# main.net
KiCad netlist of a schematic drawn in EAGLE
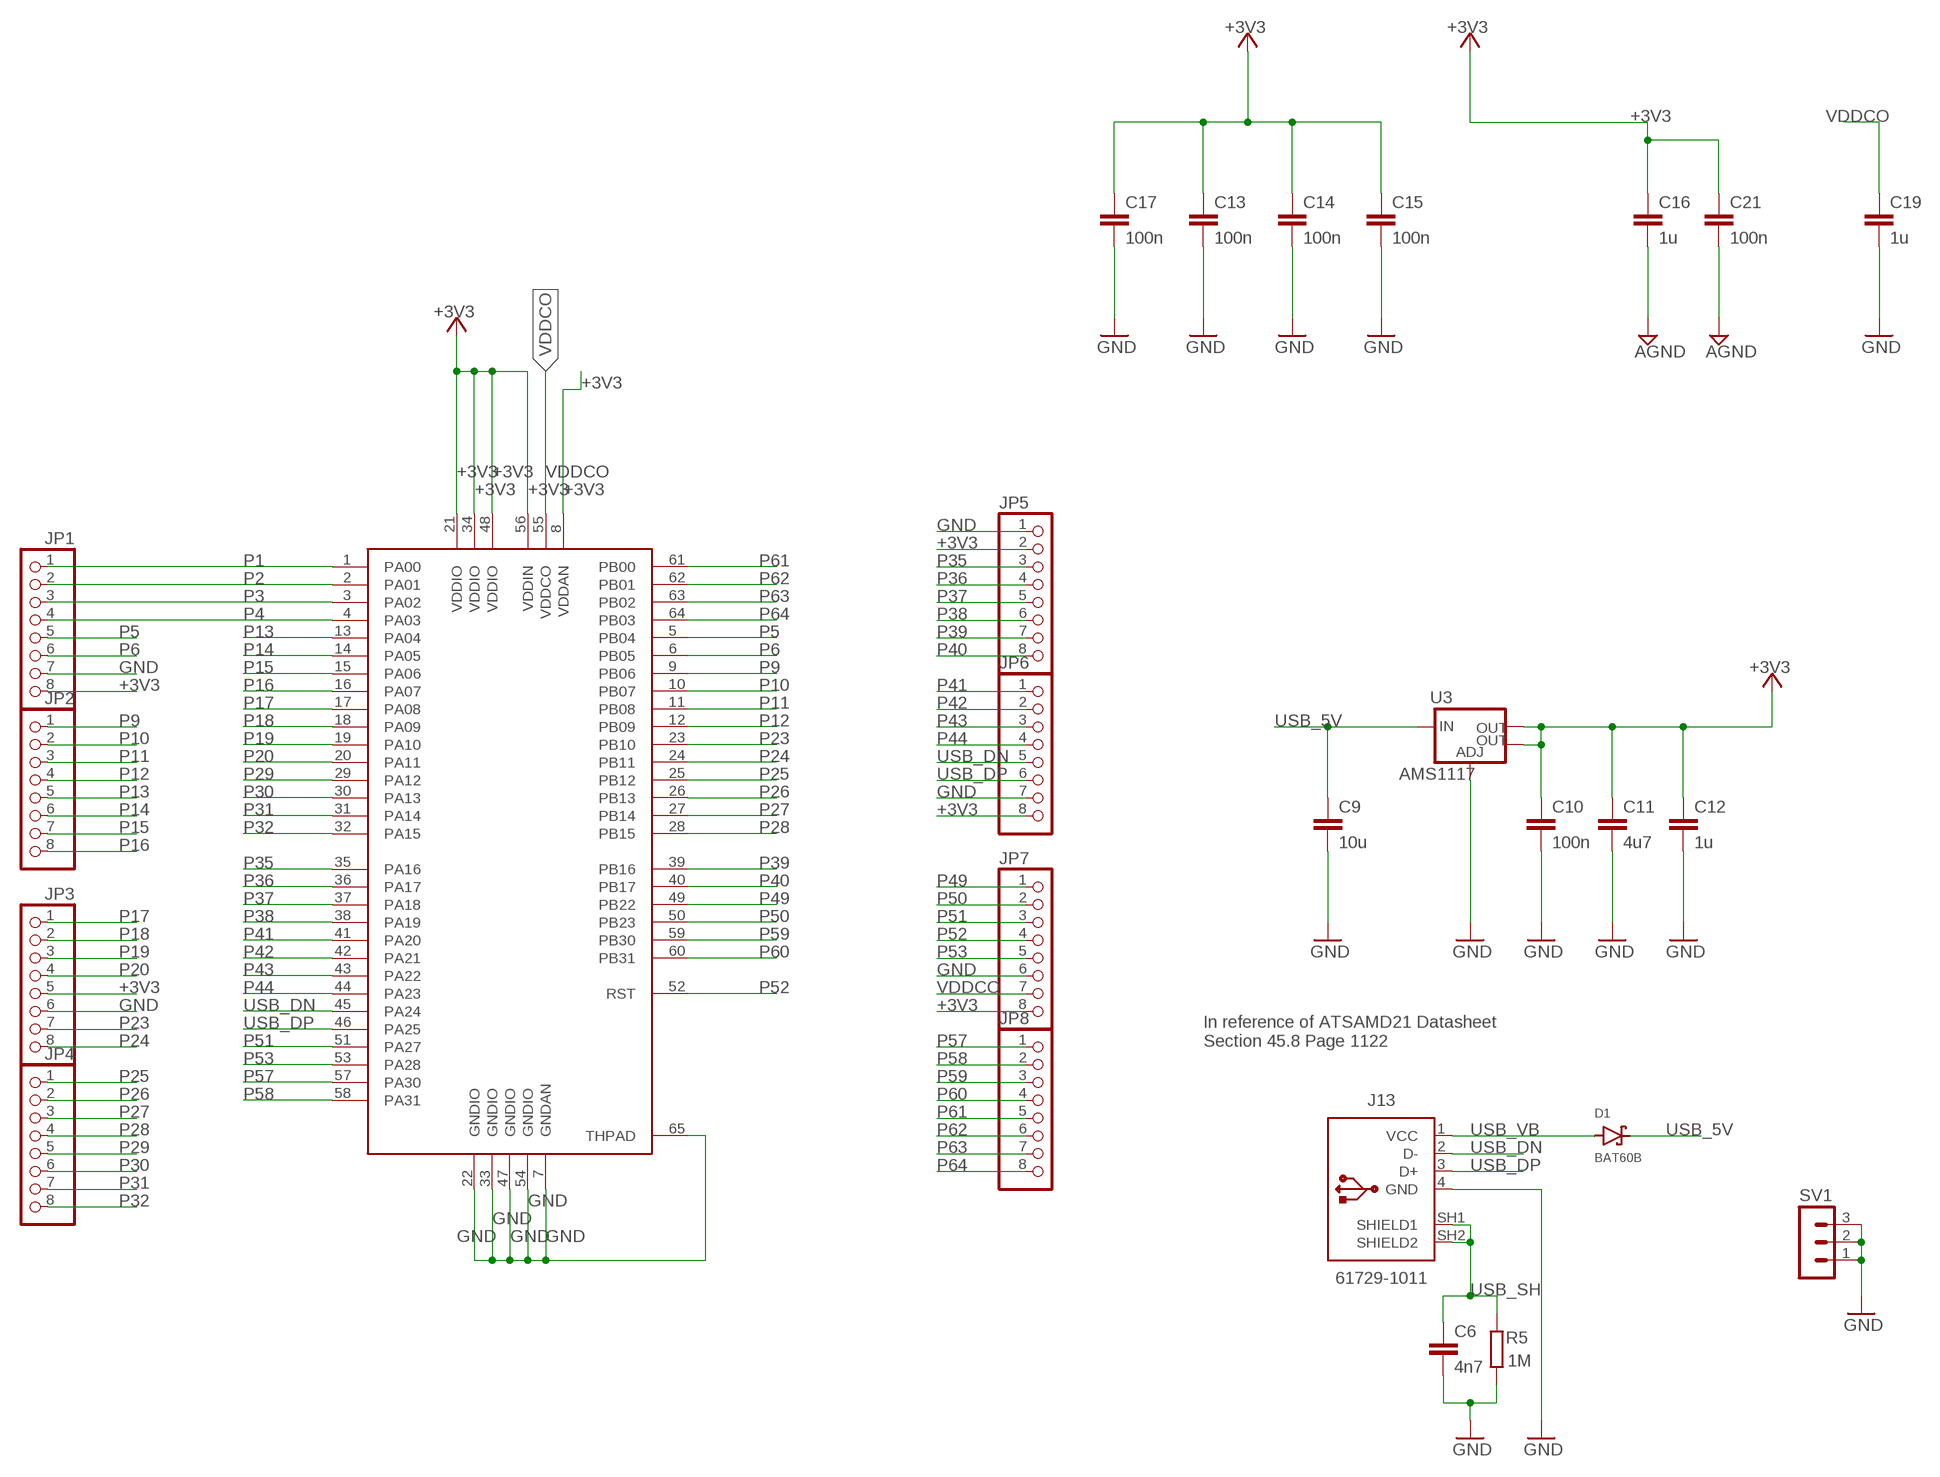
[diagram p0: schematic, sheet 1]

(export (version "E")
  (design (tool "Eeschema 10.0.6"))
  (components
    (comp (ref "C6")
      (value "4n7")
      (footprint "eagle-import:C0603")
      (libsource (lib "eagle-import") (part "C-EUC0603"))
    )
    (comp (ref "C9")
      (value "10u")
      (footprint "eagle-import:C0603")
      (libsource (lib "eagle-import") (part "C-EUC0603"))
    )
    (comp (ref "C10")
      (value "100n")
      (footprint "eagle-import:C0603")
      (libsource (lib "eagle-import") (part "C-EUC0603"))
    )
    (comp (ref "C11")
      (value "4u7")
      (footprint "eagle-import:C0603")
      (libsource (lib "eagle-import") (part "C-EUC0603"))
    )
    (comp (ref "C12")
      (value "1u")
      (footprint "eagle-import:C0603")
      (libsource (lib "eagle-import") (part "C-EUC0603"))
    )
    (comp (ref "C13")
      (value "100n")
      (footprint "eagle-import:C0603")
      (libsource (lib "eagle-import") (part "C-EUC0603"))
    )
    (comp (ref "C14")
      (value "100n")
      (footprint "eagle-import:C0603")
      (libsource (lib "eagle-import") (part "C-EUC0603"))
    )
    (comp (ref "C15")
      (value "100n")
      (footprint "eagle-import:C0603")
      (libsource (lib "eagle-import") (part "C-EUC0603"))
    )
    (comp (ref "C16")
      (value "1u")
      (footprint "eagle-import:C0603")
      (libsource (lib "eagle-import") (part "C-EUC0603"))
    )
    (comp (ref "C17")
      (value "100n")
      (footprint "eagle-import:C0603")
      (libsource (lib "eagle-import") (part "C-EUC0603"))
    )
    (comp (ref "C19")
      (value "1u")
      (footprint "eagle-import:C0603")
      (libsource (lib "eagle-import") (part "C-EUC0603"))
    )
    (comp (ref "C21")
      (value "100n")
      (footprint "eagle-import:C0603")
      (libsource (lib "eagle-import") (part "C-EUC0603"))
    )
    (comp (ref "D1")
      (value "BAT60B")
      (footprint "eagle-import:DO41-7.6")
      (libsource (lib "eagle-import") (part "1N5817-B"))
    )
    (comp (ref "J13")
      (value "61729-1011")
      (footprint "eagle-import:61729-1011BLF")
      (fields (field (name "MANUFACTURER") "Amphenol ICC (FCI)") (field (name "MPN") "61729-1011BLF"))
      (libsource (lib "eagle-import") (part "61729-1011"))
    )
    (comp (ref "JP1")
      (value "PINHD-1X8CLEANBIG")
      (footprint "eagle-import:1X08-CLEANBIG")
      (libsource (lib "eagle-import") (part "PINHD-1X8CLEANBIG"))
    )
    (comp (ref "JP2")
      (value "PINHD-1X8CLEANBIG")
      (footprint "eagle-import:1X08-CLEANBIG")
      (libsource (lib "eagle-import") (part "PINHD-1X8CLEANBIG"))
    )
    (comp (ref "JP3")
      (value "PINHD-1X8CLEANBIG")
      (footprint "eagle-import:1X08-CLEANBIG")
      (libsource (lib "eagle-import") (part "PINHD-1X8CLEANBIG"))
    )
    (comp (ref "JP4")
      (value "PINHD-1X8CLEANBIG")
      (footprint "eagle-import:1X08-CLEANBIG")
      (libsource (lib "eagle-import") (part "PINHD-1X8CLEANBIG"))
    )
    (comp (ref "JP5")
      (value "PINHD-1X8CLEANBIG")
      (footprint "eagle-import:1X08-CLEANBIG")
      (libsource (lib "eagle-import") (part "PINHD-1X8CLEANBIG"))
    )
    (comp (ref "JP6")
      (value "PINHD-1X8CLEANBIG")
      (footprint "eagle-import:1X08-CLEANBIG")
      (libsource (lib "eagle-import") (part "PINHD-1X8CLEANBIG"))
    )
    (comp (ref "JP7")
      (value "PINHD-1X8CLEANBIG")
      (footprint "eagle-import:1X08-CLEANBIG")
      (libsource (lib "eagle-import") (part "PINHD-1X8CLEANBIG"))
    )
    (comp (ref "JP8")
      (value "PINHD-1X8CLEANBIG")
      (footprint "eagle-import:1X08-CLEANBIG")
      (libsource (lib "eagle-import") (part "PINHD-1X8CLEANBIG"))
    )
    (comp (ref "R5")
      (value "1M")
      (footprint "eagle-import:R0603")
      (libsource (lib "eagle-import") (part "R-EU_R0603"))
    )
    (comp (ref "SV1")
      (value "MA03-1")
      (footprint "eagle-import:MA03-1")
      (libsource (lib "eagle-import") (part "MA03-1"))
    )
    (comp (ref "U$1")
      (value "ATSAMD21J18AQFN64")
      (footprint "eagle-import:QFN50P900X900X100-65T535")
      (libsource (lib "eagle-import") (part "ATSAMD21J18AQFN64"))
    )
    (comp (ref "U3")
      (value "AMS1117")
      (footprint "eagle-import:SOT223")
      (libsource (lib "eagle-import") (part "V_REG_LM1117SOT223"))
    )
  )
  (nets
    (net (code "1") (name "+3V3") (class "Default")
      (node (ref "C10") (pin "1") (pinfunction "1_1") (pintype "passive"))
      (node (ref "C11") (pin "1") (pinfunction "1_1") (pintype "passive"))
      (node (ref "C12") (pin "1") (pinfunction "1_1") (pintype "passive"))
      (node (ref "C13") (pin "1") (pinfunction "1_1") (pintype "passive"))
      (node (ref "C14") (pin "1") (pinfunction "1_1") (pintype "passive"))
      (node (ref "C15") (pin "1") (pinfunction "1_1") (pintype "passive"))
      (node (ref "C16") (pin "1") (pinfunction "1_1") (pintype "passive"))
      (node (ref "C17") (pin "1") (pinfunction "1_1") (pintype "passive"))
      (node (ref "C21") (pin "1") (pinfunction "1_1") (pintype "passive"))
      (node (ref "JP1") (pin "8") (pinfunction "8_8") (pintype "passive"))
      (node (ref "JP3") (pin "5") (pinfunction "5_5") (pintype "passive"))
      (node (ref "JP5") (pin "2") (pinfunction "2_2") (pintype "passive"))
      (node (ref "JP6") (pin "8") (pinfunction "8_8") (pintype "passive"))
      (node (ref "JP7") (pin "8") (pinfunction "8_8") (pintype "passive"))
      (node (ref "U$1") (pin "21") (pinfunction "VDDIO_21") (pintype "bidirectional"))
      (node (ref "U$1") (pin "34") (pinfunction "VDDIO_34") (pintype "bidirectional"))
      (node (ref "U$1") (pin "48") (pinfunction "VDDIO_48") (pintype "bidirectional"))
      (node (ref "U$1") (pin "56") (pinfunction "VDDIN_56") (pintype "bidirectional"))
      (node (ref "U$1") (pin "8") (pinfunction "VDDAN_8") (pintype "bidirectional"))
      (node (ref "U3") (pin "2") (pinfunction "OUT_2") (pintype "output"))
      (node (ref "U3") (pin "4") (pinfunction "OUT_4") (pintype "output"))
    )
    (net (code "2") (name "/P1") (class "Default")
      (node (ref "JP1") (pin "1") (pinfunction "1_1") (pintype "passive"))
      (node (ref "U$1") (pin "1") (pinfunction "PA00_1") (pintype "bidirectional"))
    )
    (net (code "3") (name "/P2") (class "Default")
      (node (ref "JP1") (pin "2") (pinfunction "2_2") (pintype "passive"))
      (node (ref "U$1") (pin "2") (pinfunction "PA01_2") (pintype "bidirectional"))
    )
    (net (code "4") (name "/P3") (class "Default")
      (node (ref "JP1") (pin "3") (pinfunction "3_3") (pintype "passive"))
      (node (ref "U$1") (pin "3") (pinfunction "PA02_3") (pintype "bidirectional"))
    )
    (net (code "5") (name "/P4") (class "Default")
      (node (ref "JP1") (pin "4") (pinfunction "4_4") (pintype "passive"))
      (node (ref "U$1") (pin "4") (pinfunction "PA03_4") (pintype "bidirectional"))
    )
    (net (code "6") (name "/P5") (class "Default")
      (node (ref "JP1") (pin "5") (pinfunction "5_5") (pintype "passive"))
      (node (ref "U$1") (pin "5") (pinfunction "PB04_5") (pintype "bidirectional"))
    )
    (net (code "7") (name "/P6") (class "Default")
      (node (ref "JP1") (pin "6") (pinfunction "6_6") (pintype "passive"))
      (node (ref "U$1") (pin "6") (pinfunction "PB05_6") (pintype "bidirectional"))
    )
    (net (code "8") (name "/P9") (class "Default")
      (node (ref "JP2") (pin "1") (pinfunction "1_1") (pintype "passive"))
      (node (ref "U$1") (pin "9") (pinfunction "PB06_9") (pintype "bidirectional"))
    )
    (net (code "9") (name "/P10") (class "Default")
      (node (ref "JP2") (pin "2") (pinfunction "2_2") (pintype "passive"))
      (node (ref "U$1") (pin "10") (pinfunction "PB07_10") (pintype "bidirectional"))
    )
    (net (code "10") (name "/P11") (class "Default")
      (node (ref "JP2") (pin "3") (pinfunction "3_3") (pintype "passive"))
      (node (ref "U$1") (pin "11") (pinfunction "PB08_11") (pintype "bidirectional"))
    )
    (net (code "11") (name "/P12") (class "Default")
      (node (ref "JP2") (pin "4") (pinfunction "4_4") (pintype "passive"))
      (node (ref "U$1") (pin "12") (pinfunction "PB09_12") (pintype "bidirectional"))
    )
    (net (code "12") (name "/P13") (class "Default")
      (node (ref "JP2") (pin "5") (pinfunction "5_5") (pintype "passive"))
      (node (ref "U$1") (pin "13") (pinfunction "PA04_13") (pintype "bidirectional"))
    )
    (net (code "13") (name "/P14") (class "Default")
      (node (ref "JP2") (pin "6") (pinfunction "6_6") (pintype "passive"))
      (node (ref "U$1") (pin "14") (pinfunction "PA05_14") (pintype "bidirectional"))
    )
    (net (code "14") (name "/P15") (class "Default")
      (node (ref "JP2") (pin "7") (pinfunction "7_7") (pintype "passive"))
      (node (ref "U$1") (pin "15") (pinfunction "PA06_15") (pintype "bidirectional"))
    )
    (net (code "15") (name "/P16") (class "Default")
      (node (ref "JP2") (pin "8") (pinfunction "8_8") (pintype "passive"))
      (node (ref "U$1") (pin "16") (pinfunction "PA07_16") (pintype "bidirectional"))
    )
    (net (code "16") (name "/P17") (class "Default")
      (node (ref "JP3") (pin "1") (pinfunction "1_1") (pintype "passive"))
      (node (ref "U$1") (pin "17") (pinfunction "PA08_17") (pintype "bidirectional"))
    )
    (net (code "17") (name "/P18") (class "Default")
      (node (ref "JP3") (pin "2") (pinfunction "2_2") (pintype "passive"))
      (node (ref "U$1") (pin "18") (pinfunction "PA09_18") (pintype "bidirectional"))
    )
    (net (code "18") (name "/P19") (class "Default")
      (node (ref "JP3") (pin "3") (pinfunction "3_3") (pintype "passive"))
      (node (ref "U$1") (pin "19") (pinfunction "PA10_19") (pintype "bidirectional"))
    )
    (net (code "19") (name "/P20") (class "Default")
      (node (ref "JP3") (pin "4") (pinfunction "4_4") (pintype "passive"))
      (node (ref "U$1") (pin "20") (pinfunction "PA11_20") (pintype "bidirectional"))
    )
    (net (code "20") (name "/P23") (class "Default")
      (node (ref "JP3") (pin "7") (pinfunction "7_7") (pintype "passive"))
      (node (ref "U$1") (pin "23") (pinfunction "PB10_23") (pintype "bidirectional"))
    )
    (net (code "21") (name "/P24") (class "Default")
      (node (ref "JP3") (pin "8") (pinfunction "8_8") (pintype "passive"))
      (node (ref "U$1") (pin "24") (pinfunction "PB11_24") (pintype "bidirectional"))
    )
    (net (code "22") (name "/P25") (class "Default")
      (node (ref "JP4") (pin "1") (pinfunction "1_1") (pintype "passive"))
      (node (ref "U$1") (pin "25") (pinfunction "PB12_25") (pintype "bidirectional"))
    )
    (net (code "23") (name "/P26") (class "Default")
      (node (ref "JP4") (pin "2") (pinfunction "2_2") (pintype "passive"))
      (node (ref "U$1") (pin "26") (pinfunction "PB13_26") (pintype "bidirectional"))
    )
    (net (code "24") (name "/P27") (class "Default")
      (node (ref "JP4") (pin "3") (pinfunction "3_3") (pintype "passive"))
      (node (ref "U$1") (pin "27") (pinfunction "PB14_27") (pintype "bidirectional"))
    )
    (net (code "25") (name "/P28") (class "Default")
      (node (ref "JP4") (pin "4") (pinfunction "4_4") (pintype "passive"))
      (node (ref "U$1") (pin "28") (pinfunction "PB15_28") (pintype "bidirectional"))
    )
    (net (code "26") (name "/P29") (class "Default")
      (node (ref "JP4") (pin "5") (pinfunction "5_5") (pintype "passive"))
      (node (ref "U$1") (pin "29") (pinfunction "PA12_29") (pintype "bidirectional"))
    )
    (net (code "27") (name "/P30") (class "Default")
      (node (ref "JP4") (pin "6") (pinfunction "6_6") (pintype "passive"))
      (node (ref "U$1") (pin "30") (pinfunction "PA13_30") (pintype "bidirectional"))
    )
    (net (code "28") (name "/P31") (class "Default")
      (node (ref "JP4") (pin "7") (pinfunction "7_7") (pintype "passive"))
      (node (ref "U$1") (pin "31") (pinfunction "PA14_31") (pintype "bidirectional"))
    )
    (net (code "29") (name "/P32") (class "Default")
      (node (ref "JP4") (pin "8") (pinfunction "8_8") (pintype "passive"))
      (node (ref "U$1") (pin "32") (pinfunction "PA15_32") (pintype "bidirectional"))
    )
    (net (code "30") (name "/P35") (class "Default")
      (node (ref "JP5") (pin "3") (pinfunction "3_3") (pintype "passive"))
      (node (ref "U$1") (pin "35") (pinfunction "PA16_35") (pintype "bidirectional"))
    )
    (net (code "31") (name "/P36") (class "Default")
      (node (ref "JP5") (pin "4") (pinfunction "4_4") (pintype "passive"))
      (node (ref "U$1") (pin "36") (pinfunction "PA17_36") (pintype "bidirectional"))
    )
    (net (code "32") (name "/P37") (class "Default")
      (node (ref "JP5") (pin "5") (pinfunction "5_5") (pintype "passive"))
      (node (ref "U$1") (pin "37") (pinfunction "PA18_37") (pintype "bidirectional"))
    )
    (net (code "33") (name "/P38") (class "Default")
      (node (ref "JP5") (pin "6") (pinfunction "6_6") (pintype "passive"))
      (node (ref "U$1") (pin "38") (pinfunction "PA19_38") (pintype "bidirectional"))
    )
    (net (code "34") (name "/P39") (class "Default")
      (node (ref "JP5") (pin "7") (pinfunction "7_7") (pintype "passive"))
      (node (ref "U$1") (pin "39") (pinfunction "PB16_39") (pintype "bidirectional"))
    )
    (net (code "35") (name "/P40") (class "Default")
      (node (ref "JP5") (pin "8") (pinfunction "8_8") (pintype "passive"))
      (node (ref "U$1") (pin "40") (pinfunction "PB17_40") (pintype "bidirectional"))
    )
    (net (code "36") (name "/P41") (class "Default")
      (node (ref "JP6") (pin "1") (pinfunction "1_1") (pintype "passive"))
      (node (ref "U$1") (pin "41") (pinfunction "PA20_41") (pintype "bidirectional"))
    )
    (net (code "37") (name "/P42") (class "Default")
      (node (ref "JP6") (pin "2") (pinfunction "2_2") (pintype "passive"))
      (node (ref "U$1") (pin "42") (pinfunction "PA21_42") (pintype "bidirectional"))
    )
    (net (code "38") (name "/P43") (class "Default")
      (node (ref "JP6") (pin "3") (pinfunction "3_3") (pintype "passive"))
      (node (ref "U$1") (pin "43") (pinfunction "PA22_43") (pintype "bidirectional"))
    )
    (net (code "39") (name "/P44") (class "Default")
      (node (ref "JP6") (pin "4") (pinfunction "4_4") (pintype "passive"))
      (node (ref "U$1") (pin "44") (pinfunction "PA23_44") (pintype "bidirectional"))
    )
    (net (code "40") (name "/P49") (class "Default")
      (node (ref "JP7") (pin "1") (pinfunction "1_1") (pintype "passive"))
      (node (ref "U$1") (pin "49") (pinfunction "PB22_49") (pintype "bidirectional"))
    )
    (net (code "41") (name "/P50") (class "Default")
      (node (ref "JP7") (pin "2") (pinfunction "2_2") (pintype "passive"))
      (node (ref "U$1") (pin "50") (pinfunction "PB23_50") (pintype "bidirectional"))
    )
    (net (code "42") (name "/P51") (class "Default")
      (node (ref "JP7") (pin "3") (pinfunction "3_3") (pintype "passive"))
      (node (ref "U$1") (pin "51") (pinfunction "PA27_51") (pintype "bidirectional"))
    )
    (net (code "43") (name "/P52") (class "Default")
      (node (ref "JP7") (pin "4") (pinfunction "4_4") (pintype "passive"))
      (node (ref "U$1") (pin "52") (pinfunction "RST_52") (pintype "bidirectional"))
    )
    (net (code "44") (name "/P53") (class "Default")
      (node (ref "JP7") (pin "5") (pinfunction "5_5") (pintype "passive"))
      (node (ref "U$1") (pin "53") (pinfunction "PA28_53") (pintype "bidirectional"))
    )
    (net (code "45") (name "/P57") (class "Default")
      (node (ref "JP8") (pin "1") (pinfunction "1_1") (pintype "passive"))
      (node (ref "U$1") (pin "57") (pinfunction "PA30_57") (pintype "bidirectional"))
    )
    (net (code "46") (name "/P58") (class "Default")
      (node (ref "JP8") (pin "2") (pinfunction "2_2") (pintype "passive"))
      (node (ref "U$1") (pin "58") (pinfunction "PA31_58") (pintype "bidirectional"))
    )
    (net (code "47") (name "/P59") (class "Default")
      (node (ref "JP8") (pin "3") (pinfunction "3_3") (pintype "passive"))
      (node (ref "U$1") (pin "59") (pinfunction "PB30_59") (pintype "bidirectional"))
    )
    (net (code "48") (name "/P60") (class "Default")
      (node (ref "JP8") (pin "4") (pinfunction "4_4") (pintype "passive"))
      (node (ref "U$1") (pin "60") (pinfunction "PB31_60") (pintype "bidirectional"))
    )
    (net (code "49") (name "/P61") (class "Default")
      (node (ref "JP8") (pin "5") (pinfunction "5_5") (pintype "passive"))
      (node (ref "U$1") (pin "61") (pinfunction "PB00_61") (pintype "bidirectional"))
    )
    (net (code "50") (name "/P62") (class "Default")
      (node (ref "JP8") (pin "6") (pinfunction "6_6") (pintype "passive"))
      (node (ref "U$1") (pin "62") (pinfunction "PB01_62") (pintype "bidirectional"))
    )
    (net (code "51") (name "/P63") (class "Default")
      (node (ref "JP8") (pin "7") (pinfunction "7_7") (pintype "passive"))
      (node (ref "U$1") (pin "63") (pinfunction "PB02_63") (pintype "bidirectional"))
    )
    (net (code "52") (name "/P64") (class "Default")
      (node (ref "JP8") (pin "8") (pinfunction "8_8") (pintype "passive"))
      (node (ref "U$1") (pin "64") (pinfunction "PB03_64") (pintype "bidirectional"))
    )
    (net (code "53") (name "/USB_5V") (class "Default")
      (node (ref "C9") (pin "1") (pinfunction "1_1") (pintype "passive"))
      (node (ref "D1") (pin "C") (pinfunction "C_C") (pintype "passive"))
      (node (ref "U3") (pin "3") (pinfunction "IN_3") (pintype "input"))
    )
    (net (code "54") (name "/USB_DN") (class "Default")
      (node (ref "J13") (pin "2") (pinfunction "D-_2") (pintype "bidirectional"))
      (node (ref "JP6") (pin "5") (pinfunction "5_5") (pintype "passive"))
      (node (ref "U$1") (pin "45") (pinfunction "PA24_45") (pintype "bidirectional"))
    )
    (net (code "55") (name "/USB_DP") (class "Default")
      (node (ref "J13") (pin "3") (pinfunction "D+_3") (pintype "bidirectional"))
      (node (ref "JP6") (pin "6") (pinfunction "6_6") (pintype "passive"))
      (node (ref "U$1") (pin "46") (pinfunction "PA25_46") (pintype "bidirectional"))
    )
    (net (code "56") (name "/USB_SH") (class "Default")
      (node (ref "C6") (pin "1") (pinfunction "1_1") (pintype "passive"))
      (node (ref "J13") (pin "SH1") (pinfunction "SHIELD1_SH1") (pintype "power_in"))
      (node (ref "J13") (pin "SH2") (pinfunction "SHIELD2_SH2") (pintype "power_in"))
      (node (ref "R5") (pin "1") (pinfunction "1_1") (pintype "passive"))
    )
    (net (code "57") (name "/USB_VB") (class "Default")
      (node (ref "D1") (pin "A") (pinfunction "A_A") (pintype "passive"))
      (node (ref "J13") (pin "1") (pinfunction "VCC_1") (pintype "power_in"))
    )
    (net (code "58") (name "AGND") (class "Default")
      (node (ref "C10") (pin "2") (pinfunction "2_2") (pintype "passive"))
      (node (ref "C11") (pin "2") (pinfunction "2_2") (pintype "passive"))
      (node (ref "C12") (pin "2") (pinfunction "2_2") (pintype "passive"))
      (node (ref "C13") (pin "2") (pinfunction "2_2") (pintype "passive"))
      (node (ref "C14") (pin "2") (pinfunction "2_2") (pintype "passive"))
      (node (ref "C15") (pin "2") (pinfunction "2_2") (pintype "passive"))
      (node (ref "C16") (pin "2") (pinfunction "2_2") (pintype "passive"))
      (node (ref "C17") (pin "2") (pinfunction "2_2") (pintype "passive"))
      (node (ref "C19") (pin "2") (pinfunction "2_2") (pintype "passive"))
      (node (ref "C21") (pin "2") (pinfunction "2_2") (pintype "passive"))
      (node (ref "C6") (pin "2") (pinfunction "2_2") (pintype "passive"))
      (node (ref "C9") (pin "2") (pinfunction "2_2") (pintype "passive"))
      (node (ref "J13") (pin "4") (pinfunction "GND_4") (pintype "power_in"))
      (node (ref "JP1") (pin "7") (pinfunction "7_7") (pintype "passive"))
      (node (ref "JP3") (pin "6") (pinfunction "6_6") (pintype "passive"))
      (node (ref "JP5") (pin "1") (pinfunction "1_1") (pintype "passive"))
      (node (ref "JP6") (pin "7") (pinfunction "7_7") (pintype "passive"))
      (node (ref "JP7") (pin "6") (pinfunction "6_6") (pintype "passive"))
      (node (ref "R5") (pin "2") (pinfunction "2_2") (pintype "passive"))
      (node (ref "SV1") (pin "1") (pinfunction "1_1") (pintype "passive"))
      (node (ref "SV1") (pin "2") (pinfunction "2_2") (pintype "passive"))
      (node (ref "SV1") (pin "3") (pinfunction "3_3") (pintype "passive"))
      (node (ref "U$1") (pin "22") (pinfunction "GNDIO_22") (pintype "bidirectional"))
      (node (ref "U$1") (pin "33") (pinfunction "GNDIO_33") (pintype "bidirectional"))
      (node (ref "U$1") (pin "47") (pinfunction "GNDIO_47") (pintype "bidirectional"))
      (node (ref "U$1") (pin "54") (pinfunction "GNDIO_54") (pintype "bidirectional"))
      (node (ref "U$1") (pin "65") (pinfunction "THPAD_65") (pintype "bidirectional"))
      (node (ref "U$1") (pin "7") (pinfunction "GNDAN_7") (pintype "bidirectional"))
      (node (ref "U3") (pin "1") (pinfunction "ADJ_1") (pintype "input"))
    )
    (net (code "59") (name "VDDCO") (class "Default")
      (node (ref "C19") (pin "1") (pinfunction "1_1") (pintype "passive"))
      (node (ref "JP7") (pin "7") (pinfunction "7_7") (pintype "passive"))
      (node (ref "U$1") (pin "55") (pinfunction "VDDCO_55") (pintype "bidirectional"))
    )
  )
)
